# address_LEDs.net
KiCad netlist of a schematic drawn in Altium Designer
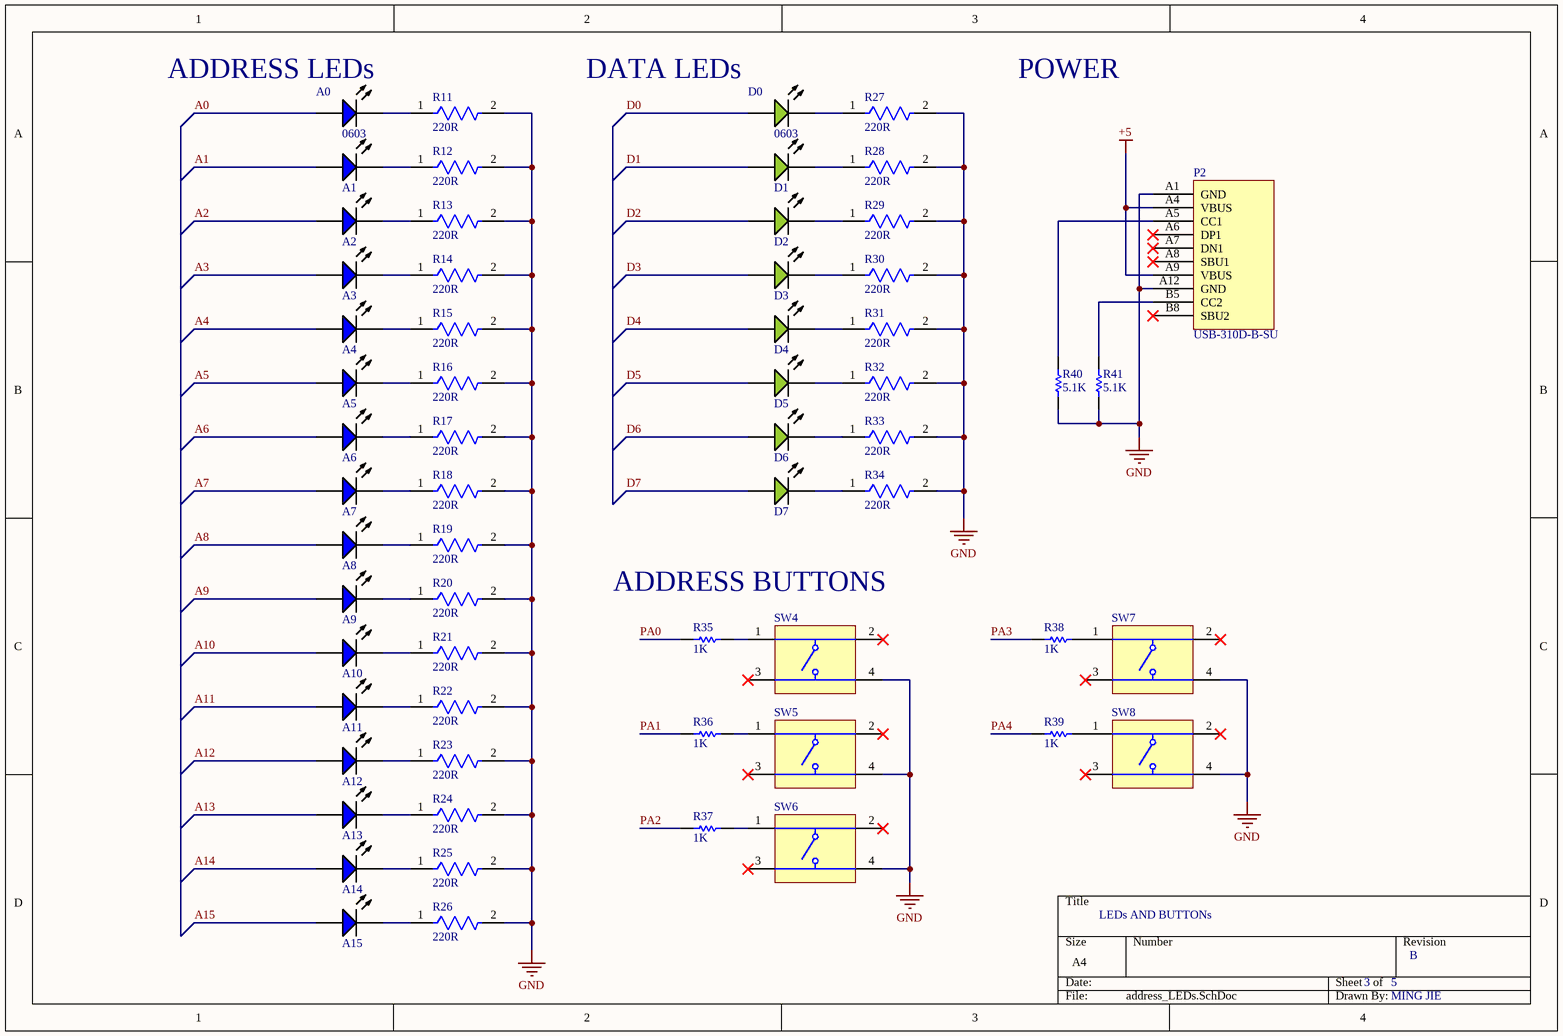
[diagram p0: address_LEDs.SchDoc]

(export (version "E")
  (design (tool "Eeschema 10.0.6"))
  (components
    (comp (ref "A0")
      (value "19-217/BHC-ZL1M2RY/3T")
      (footprint "EVRL-0603-2_V")
      (description "Chip LED, Blue, 5 V, 25 mA, -40 to 85 degC, 2-Pin SMD (0603), RoHS, Tape and Reel")
      (fields (field (name "PACKAGE REFERENCE") "0603") (field (name "MANUFACTURER") "Everlight Electronics"))
      (libsource (lib "Altium Content Vault") (part "LED-BLUE-AK-2"))
    )
    (comp (ref "A1")
      (value "19-217/BHC-ZL1M2RY/3T")
      (footprint "EVRL-0603-2_V")
      (description "Chip LED, Blue, 5 V, 25 mA, -40 to 85 degC, 2-Pin SMD (0603), RoHS, Tape and Reel")
      (fields (field (name "MANUFACTURER") "Everlight Electronics"))
      (libsource (lib "Altium Content Vault") (part "LED-BLUE-AK-2"))
    )
    (comp (ref "A2")
      (value "19-217/BHC-ZL1M2RY/3T")
      (footprint "EVRL-0603-2_V")
      (description "Chip LED, Blue, 5 V, 25 mA, -40 to 85 degC, 2-Pin SMD (0603), RoHS, Tape and Reel")
      (fields (field (name "MANUFACTURER") "Everlight Electronics"))
      (libsource (lib "Altium Content Vault") (part "LED-BLUE-AK-2"))
    )
    (comp (ref "A3")
      (value "19-217/BHC-ZL1M2RY/3T")
      (footprint "EVRL-0603-2_V")
      (description "Chip LED, Blue, 5 V, 25 mA, -40 to 85 degC, 2-Pin SMD (0603), RoHS, Tape and Reel")
      (fields (field (name "MANUFACTURER") "Everlight Electronics"))
      (libsource (lib "Altium Content Vault") (part "LED-BLUE-AK-2"))
    )
    (comp (ref "A4")
      (value "19-217/BHC-ZL1M2RY/3T")
      (footprint "EVRL-0603-2_V")
      (description "Chip LED, Blue, 5 V, 25 mA, -40 to 85 degC, 2-Pin SMD (0603), RoHS, Tape and Reel")
      (fields (field (name "MANUFACTURER") "Everlight Electronics"))
      (libsource (lib "Altium Content Vault") (part "LED-BLUE-AK-2"))
    )
    (comp (ref "A5")
      (value "19-217/BHC-ZL1M2RY/3T")
      (footprint "EVRL-0603-2_V")
      (description "Chip LED, Blue, 5 V, 25 mA, -40 to 85 degC, 2-Pin SMD (0603), RoHS, Tape and Reel")
      (fields (field (name "MANUFACTURER") "Everlight Electronics"))
      (libsource (lib "Altium Content Vault") (part "LED-BLUE-AK-2"))
    )
    (comp (ref "A6")
      (value "19-217/BHC-ZL1M2RY/3T")
      (footprint "EVRL-0603-2_V")
      (description "Chip LED, Blue, 5 V, 25 mA, -40 to 85 degC, 2-Pin SMD (0603), RoHS, Tape and Reel")
      (fields (field (name "MANUFACTURER") "Everlight Electronics"))
      (libsource (lib "Altium Content Vault") (part "LED-BLUE-AK-2"))
    )
    (comp (ref "A7")
      (value "19-217/BHC-ZL1M2RY/3T")
      (footprint "EVRL-0603-2_V")
      (description "Chip LED, Blue, 5 V, 25 mA, -40 to 85 degC, 2-Pin SMD (0603), RoHS, Tape and Reel")
      (fields (field (name "MANUFACTURER") "Everlight Electronics"))
      (libsource (lib "Altium Content Vault") (part "LED-BLUE-AK-2"))
    )
    (comp (ref "A8")
      (value "19-217/BHC-ZL1M2RY/3T")
      (footprint "EVRL-0603-2_V")
      (description "Chip LED, Blue, 5 V, 25 mA, -40 to 85 degC, 2-Pin SMD (0603), RoHS, Tape and Reel")
      (fields (field (name "MANUFACTURER") "Everlight Electronics"))
      (libsource (lib "Altium Content Vault") (part "LED-BLUE-AK-2"))
    )
    (comp (ref "A9")
      (value "19-217/BHC-ZL1M2RY/3T")
      (footprint "EVRL-0603-2_V")
      (description "Chip LED, Blue, 5 V, 25 mA, -40 to 85 degC, 2-Pin SMD (0603), RoHS, Tape and Reel")
      (fields (field (name "MANUFACTURER") "Everlight Electronics"))
      (libsource (lib "Altium Content Vault") (part "LED-BLUE-AK-2"))
    )
    (comp (ref "A10")
      (value "19-217/BHC-ZL1M2RY/3T")
      (footprint "EVRL-0603-2_V")
      (description "Chip LED, Blue, 5 V, 25 mA, -40 to 85 degC, 2-Pin SMD (0603), RoHS, Tape and Reel")
      (fields (field (name "MANUFACTURER") "Everlight Electronics"))
      (libsource (lib "Altium Content Vault") (part "LED-BLUE-AK-2"))
    )
    (comp (ref "A11")
      (value "19-217/BHC-ZL1M2RY/3T")
      (footprint "EVRL-0603-2_V")
      (description "Chip LED, Blue, 5 V, 25 mA, -40 to 85 degC, 2-Pin SMD (0603), RoHS, Tape and Reel")
      (fields (field (name "MANUFACTURER") "Everlight Electronics"))
      (libsource (lib "Altium Content Vault") (part "LED-BLUE-AK-2"))
    )
    (comp (ref "A12")
      (value "19-217/BHC-ZL1M2RY/3T")
      (footprint "EVRL-0603-2_V")
      (description "Chip LED, Blue, 5 V, 25 mA, -40 to 85 degC, 2-Pin SMD (0603), RoHS, Tape and Reel")
      (fields (field (name "MANUFACTURER") "Everlight Electronics"))
      (libsource (lib "Altium Content Vault") (part "LED-BLUE-AK-2"))
    )
    (comp (ref "A13")
      (value "19-217/BHC-ZL1M2RY/3T")
      (footprint "EVRL-0603-2_V")
      (description "Chip LED, Blue, 5 V, 25 mA, -40 to 85 degC, 2-Pin SMD (0603), RoHS, Tape and Reel")
      (fields (field (name "MANUFACTURER") "Everlight Electronics"))
      (libsource (lib "Altium Content Vault") (part "LED-BLUE-AK-2"))
    )
    (comp (ref "A14")
      (value "19-217/BHC-ZL1M2RY/3T")
      (footprint "EVRL-0603-2_V")
      (description "Chip LED, Blue, 5 V, 25 mA, -40 to 85 degC, 2-Pin SMD (0603), RoHS, Tape and Reel")
      (fields (field (name "MANUFACTURER") "Everlight Electronics"))
      (libsource (lib "Altium Content Vault") (part "LED-BLUE-AK-2"))
    )
    (comp (ref "A15")
      (value "19-217/BHC-ZL1M2RY/3T")
      (footprint "EVRL-0603-2_V")
      (description "Chip LED, Blue, 5 V, 25 mA, -40 to 85 degC, 2-Pin SMD (0603), RoHS, Tape and Reel")
      (fields (field (name "MANUFACTURER") "Everlight Electronics"))
      (libsource (lib "Altium Content Vault") (part "LED-BLUE-AK-2"))
    )
    (comp (ref "D0")
      (value "19-217/GHC-YR1S2/3T")
      (footprint "EVRL-0603-2_V")
      (description "Green 520~535nm 0603 Light Emitting Diodes (LED) RoHS")
      (fields (field (name "MANUFACTURER") "Everlight Electronics") (field (name "PACKAGE REFERENCE") "0603"))
      (libsource (lib "Altium Content Vault") (part "LED-YELLOW-GREEN-AK-2"))
    )
    (comp (ref "D1")
      (value "19-217/GHC-YR1S2/3T")
      (footprint "EVRL-0603-2_V")
      (description "Green 520~535nm 0603 Light Emitting Diodes (LED) RoHS")
      (fields (field (name "MANUFACTURER") "Everlight Electronics"))
      (libsource (lib "Altium Content Vault") (part "LED-YELLOW-GREEN-AK-2"))
    )
    (comp (ref "D2")
      (value "19-217/GHC-YR1S2/3T")
      (footprint "EVRL-0603-2_V")
      (description "Green 520~535nm 0603 Light Emitting Diodes (LED) RoHS")
      (fields (field (name "MANUFACTURER") "Everlight Electronics"))
      (libsource (lib "Altium Content Vault") (part "LED-YELLOW-GREEN-AK-2"))
    )
    (comp (ref "D3")
      (value "19-217/GHC-YR1S2/3T")
      (footprint "EVRL-0603-2_V")
      (description "Green 520~535nm 0603 Light Emitting Diodes (LED) RoHS")
      (fields (field (name "MANUFACTURER") "Everlight Electronics"))
      (libsource (lib "Altium Content Vault") (part "LED-YELLOW-GREEN-AK-2"))
    )
    (comp (ref "D4")
      (value "19-217/GHC-YR1S2/3T")
      (footprint "EVRL-0603-2_V")
      (description "Green 520~535nm 0603 Light Emitting Diodes (LED) RoHS")
      (fields (field (name "MANUFACTURER") "Everlight Electronics"))
      (libsource (lib "Altium Content Vault") (part "LED-YELLOW-GREEN-AK-2"))
    )
    (comp (ref "D5")
      (value "19-217/GHC-YR1S2/3T")
      (footprint "EVRL-0603-2_V")
      (description "Green 520~535nm 0603 Light Emitting Diodes (LED) RoHS")
      (fields (field (name "MANUFACTURER") "Everlight Electronics"))
      (libsource (lib "Altium Content Vault") (part "LED-YELLOW-GREEN-AK-2"))
    )
    (comp (ref "D6")
      (value "19-217/GHC-YR1S2/3T")
      (footprint "EVRL-0603-2_V")
      (description "Green 520~535nm 0603 Light Emitting Diodes (LED) RoHS")
      (fields (field (name "MANUFACTURER") "Everlight Electronics"))
      (libsource (lib "Altium Content Vault") (part "LED-YELLOW-GREEN-AK-2"))
    )
    (comp (ref "D7")
      (value "19-217/GHC-YR1S2/3T")
      (footprint "EVRL-0603-2_V")
      (description "Green 520~535nm 0603 Light Emitting Diodes (LED) RoHS")
      (fields (field (name "MANUFACTURER") "Everlight Electronics"))
      (libsource (lib "Altium Content Vault") (part "LED-YELLOW-GREEN-AK-2"))
    )
    (comp (ref "P2")
      (value "USB-310D-B-SU")
      (footprint "USB-C-THT")
      (description "USB Type C Receptacle")
      (libsource (lib "6502_lib") (part "USB-310D-B-SU"))
    )
    (comp (ref "R11")
      (value "CRCW0805220RFKEA")
      (footprint "FP-CRCW0805-e3-MFG")
      (description "RES Thick Film, 220Ω, 1%, 0.125W, 100ppm/°C, 0805")
      (fields (field (name "RESISTANCE") "220R") (field (name "TOLERANCE") "1%"))
      (libsource (lib "Altium Content Vault") (part "1029c3af85768c4190bb7ad29bc67b5"))
    )
    (comp (ref "R12")
      (value "CRCW0805220RFKEA")
      (footprint "FP-CRCW0805-e3-MFG")
      (description "RES Thick Film, 220Ω, 1%, 0.125W, 100ppm/°C, 0805")
      (fields (field (name "RESISTANCE") "220R") (field (name "TOLERANCE") "1%"))
      (libsource (lib "Altium Content Vault") (part "1029c3af85768c4190bb7ad29bc67b5"))
    )
    (comp (ref "R13")
      (value "CRCW0805220RFKEA")
      (footprint "FP-CRCW0805-e3-MFG")
      (description "RES Thick Film, 220Ω, 1%, 0.125W, 100ppm/°C, 0805")
      (fields (field (name "RESISTANCE") "220R") (field (name "TOLERANCE") "1%"))
      (libsource (lib "Altium Content Vault") (part "1029c3af85768c4190bb7ad29bc67b5"))
    )
    (comp (ref "R14")
      (value "CRCW0805220RFKEA")
      (footprint "FP-CRCW0805-e3-MFG")
      (description "RES Thick Film, 220Ω, 1%, 0.125W, 100ppm/°C, 0805")
      (fields (field (name "RESISTANCE") "220R") (field (name "TOLERANCE") "1%"))
      (libsource (lib "Altium Content Vault") (part "1029c3af85768c4190bb7ad29bc67b5"))
    )
    (comp (ref "R15")
      (value "CRCW0805220RFKEA")
      (footprint "FP-CRCW0805-e3-MFG")
      (description "RES Thick Film, 220Ω, 1%, 0.125W, 100ppm/°C, 0805")
      (fields (field (name "RESISTANCE") "220R") (field (name "TOLERANCE") "1%"))
      (libsource (lib "Altium Content Vault") (part "1029c3af85768c4190bb7ad29bc67b5"))
    )
    (comp (ref "R16")
      (value "CRCW0805220RFKEA")
      (footprint "FP-CRCW0805-e3-MFG")
      (description "RES Thick Film, 220Ω, 1%, 0.125W, 100ppm/°C, 0805")
      (fields (field (name "RESISTANCE") "220R") (field (name "TOLERANCE") "1%"))
      (libsource (lib "Altium Content Vault") (part "1029c3af85768c4190bb7ad29bc67b5"))
    )
    (comp (ref "R17")
      (value "CRCW0805220RFKEA")
      (footprint "FP-CRCW0805-e3-MFG")
      (description "RES Thick Film, 220Ω, 1%, 0.125W, 100ppm/°C, 0805")
      (fields (field (name "RESISTANCE") "220R") (field (name "TOLERANCE") "1%"))
      (libsource (lib "Altium Content Vault") (part "1029c3af85768c4190bb7ad29bc67b5"))
    )
    (comp (ref "R18")
      (value "CRCW0805220RFKEA")
      (footprint "FP-CRCW0805-e3-MFG")
      (description "RES Thick Film, 220Ω, 1%, 0.125W, 100ppm/°C, 0805")
      (fields (field (name "RESISTANCE") "220R") (field (name "TOLERANCE") "1%"))
      (libsource (lib "Altium Content Vault") (part "1029c3af85768c4190bb7ad29bc67b5"))
    )
    (comp (ref "R19")
      (value "CRCW0805220RFKEA")
      (footprint "FP-CRCW0805-e3-MFG")
      (description "RES Thick Film, 220Ω, 1%, 0.125W, 100ppm/°C, 0805")
      (fields (field (name "RESISTANCE") "220R") (field (name "TOLERANCE") "1%"))
      (libsource (lib "Altium Content Vault") (part "1029c3af85768c4190bb7ad29bc67b5"))
    )
    (comp (ref "R20")
      (value "CRCW0805220RFKEA")
      (footprint "FP-CRCW0805-e3-MFG")
      (description "RES Thick Film, 220Ω, 1%, 0.125W, 100ppm/°C, 0805")
      (fields (field (name "RESISTANCE") "220R") (field (name "TOLERANCE") "1%"))
      (libsource (lib "Altium Content Vault") (part "1029c3af85768c4190bb7ad29bc67b5"))
    )
    (comp (ref "R21")
      (value "CRCW0805220RFKEA")
      (footprint "FP-CRCW0805-e3-MFG")
      (description "RES Thick Film, 220Ω, 1%, 0.125W, 100ppm/°C, 0805")
      (fields (field (name "RESISTANCE") "220R") (field (name "TOLERANCE") "1%"))
      (libsource (lib "Altium Content Vault") (part "1029c3af85768c4190bb7ad29bc67b5"))
    )
    (comp (ref "R22")
      (value "CRCW0805220RFKEA")
      (footprint "FP-CRCW0805-e3-MFG")
      (description "RES Thick Film, 220Ω, 1%, 0.125W, 100ppm/°C, 0805")
      (fields (field (name "RESISTANCE") "220R") (field (name "TOLERANCE") "1%"))
      (libsource (lib "Altium Content Vault") (part "1029c3af85768c4190bb7ad29bc67b5"))
    )
    (comp (ref "R23")
      (value "CRCW0805220RFKEA")
      (footprint "FP-CRCW0805-e3-MFG")
      (description "RES Thick Film, 220Ω, 1%, 0.125W, 100ppm/°C, 0805")
      (fields (field (name "RESISTANCE") "220R") (field (name "TOLERANCE") "1%"))
      (libsource (lib "Altium Content Vault") (part "1029c3af85768c4190bb7ad29bc67b5"))
    )
    (comp (ref "R24")
      (value "CRCW0805220RFKEA")
      (footprint "FP-CRCW0805-e3-MFG")
      (description "RES Thick Film, 220Ω, 1%, 0.125W, 100ppm/°C, 0805")
      (fields (field (name "RESISTANCE") "220R") (field (name "TOLERANCE") "1%"))
      (libsource (lib "Altium Content Vault") (part "1029c3af85768c4190bb7ad29bc67b5"))
    )
    (comp (ref "R25")
      (value "CRCW0805220RFKEA")
      (footprint "FP-CRCW0805-e3-MFG")
      (description "RES Thick Film, 220Ω, 1%, 0.125W, 100ppm/°C, 0805")
      (fields (field (name "RESISTANCE") "220R") (field (name "TOLERANCE") "1%"))
      (libsource (lib "Altium Content Vault") (part "1029c3af85768c4190bb7ad29bc67b5"))
    )
    (comp (ref "R26")
      (value "CRCW0805220RFKEA")
      (footprint "FP-CRCW0805-e3-MFG")
      (description "RES Thick Film, 220Ω, 1%, 0.125W, 100ppm/°C, 0805")
      (fields (field (name "RESISTANCE") "220R") (field (name "TOLERANCE") "1%"))
      (libsource (lib "Altium Content Vault") (part "1029c3af85768c4190bb7ad29bc67b5"))
    )
    (comp (ref "R27")
      (value "CRCW0805220RFKEA")
      (footprint "FP-CRCW0805-e3-MFG")
      (description "RES Thick Film, 220Ω, 1%, 0.125W, 100ppm/°C, 0805")
      (fields (field (name "RESISTANCE") "220R") (field (name "TOLERANCE") "1%"))
      (libsource (lib "Altium Content Vault") (part "1029c3af85768c4190bb7ad29bc67b5"))
    )
    (comp (ref "R28")
      (value "CRCW0805220RFKEA")
      (footprint "FP-CRCW0805-e3-MFG")
      (description "RES Thick Film, 220Ω, 1%, 0.125W, 100ppm/°C, 0805")
      (fields (field (name "RESISTANCE") "220R") (field (name "TOLERANCE") "1%"))
      (libsource (lib "Altium Content Vault") (part "1029c3af85768c4190bb7ad29bc67b5"))
    )
    (comp (ref "R29")
      (value "CRCW0805220RFKEA")
      (footprint "FP-CRCW0805-e3-MFG")
      (description "RES Thick Film, 220Ω, 1%, 0.125W, 100ppm/°C, 0805")
      (fields (field (name "RESISTANCE") "220R") (field (name "TOLERANCE") "1%"))
      (libsource (lib "Altium Content Vault") (part "1029c3af85768c4190bb7ad29bc67b5"))
    )
    (comp (ref "R30")
      (value "CRCW0805220RFKEA")
      (footprint "FP-CRCW0805-e3-MFG")
      (description "RES Thick Film, 220Ω, 1%, 0.125W, 100ppm/°C, 0805")
      (fields (field (name "RESISTANCE") "220R") (field (name "TOLERANCE") "1%"))
      (libsource (lib "Altium Content Vault") (part "1029c3af85768c4190bb7ad29bc67b5"))
    )
    (comp (ref "R31")
      (value "CRCW0805220RFKEA")
      (footprint "FP-CRCW0805-e3-MFG")
      (description "RES Thick Film, 220Ω, 1%, 0.125W, 100ppm/°C, 0805")
      (fields (field (name "RESISTANCE") "220R") (field (name "TOLERANCE") "1%"))
      (libsource (lib "Altium Content Vault") (part "1029c3af85768c4190bb7ad29bc67b5"))
    )
    (comp (ref "R32")
      (value "CRCW0805220RFKEA")
      (footprint "FP-CRCW0805-e3-MFG")
      (description "RES Thick Film, 220Ω, 1%, 0.125W, 100ppm/°C, 0805")
      (fields (field (name "RESISTANCE") "220R") (field (name "TOLERANCE") "1%"))
      (libsource (lib "Altium Content Vault") (part "1029c3af85768c4190bb7ad29bc67b5"))
    )
    (comp (ref "R33")
      (value "CRCW0805220RFKEA")
      (footprint "FP-CRCW0805-e3-MFG")
      (description "RES Thick Film, 220Ω, 1%, 0.125W, 100ppm/°C, 0805")
      (fields (field (name "RESISTANCE") "220R") (field (name "TOLERANCE") "1%"))
      (libsource (lib "Altium Content Vault") (part "1029c3af85768c4190bb7ad29bc67b5"))
    )
    (comp (ref "R34")
      (value "CRCW0805220RFKEA")
      (footprint "FP-CRCW0805-e3-MFG")
      (description "RES Thick Film, 220Ω, 1%, 0.125W, 100ppm/°C, 0805")
      (fields (field (name "RESISTANCE") "220R") (field (name "TOLERANCE") "1%"))
      (libsource (lib "Altium Content Vault") (part "1029c3af85768c4190bb7ad29bc67b5"))
    )
    (comp (ref "R35")
      (value "CRCW08051K00FKEA")
      (footprint "RESC2013X50X30NL20T20")
      (fields (field (name "MANUFACTURER") "Vishay Dale") (field (name "RESISTANCE") "1K"))
      (libsource (lib "Altium Content Vault") (part "RES"))
    )
    (comp (ref "R36")
      (value "CRCW08051K00FKEA")
      (footprint "RESC2013X50X30NL20T20")
      (fields (field (name "MANUFACTURER") "Vishay Dale") (field (name "RESISTANCE") "1K"))
      (libsource (lib "Altium Content Vault") (part "RES"))
    )
    (comp (ref "R37")
      (value "CRCW08051K00FKEA")
      (footprint "RESC2013X50X30NL20T20")
      (fields (field (name "MANUFACTURER") "Vishay Dale") (field (name "RESISTANCE") "1K"))
      (libsource (lib "Altium Content Vault") (part "RES"))
    )
    (comp (ref "R38")
      (value "CRCW08051K00FKEA")
      (footprint "RESC2013X50X30NL20T20")
      (fields (field (name "MANUFACTURER") "Vishay Dale") (field (name "RESISTANCE") "1K"))
      (libsource (lib "Altium Content Vault") (part "RES"))
    )
    (comp (ref "R39")
      (value "CRCW08051K00FKEA")
      (footprint "RESC2013X50X30NL20T20")
      (fields (field (name "MANUFACTURER") "Vishay Dale") (field (name "RESISTANCE") "1K"))
      (libsource (lib "Altium Content Vault") (part "RES"))
    )
    (comp (ref "R40")
      (value "0805W8F5101T5E")
      (footprint "RESC2013X50X30NL20T20")
      (description "5.1kΩ ±1% 0.125W ±100ppm/℃ 0805 Chip Resistor - Surface Mount RoHS")
      (fields (field (name "MANUFACTURER") "UniOhm") (field (name "RESISTANCE") "5.1K"))
      (libsource (lib "Altium Content Vault") (part "RES"))
    )
    (comp (ref "R41")
      (value "0805W8F5101T5E")
      (footprint "RESC2013X50X30NL20T20")
      (description "5.1kΩ ±1% 0.125W ±100ppm/℃ 0805 Chip Resistor - Surface Mount RoHS")
      (fields (field (name "MANUFACTURER") "UniOhm") (field (name "RESISTANCE") "5.1K"))
      (libsource (lib "Altium Content Vault") (part "RES"))
    )
    (comp (ref "SW4")
      (value "K2-1102SP-C4SC-04")
      (footprint "TECO-FSM4JSMA_V")
      (description "Swicth, SPST, 24 V, -35 to 85 degC, 4-Pin SMD, RoHS, Tape and Reel")
      (fields (field (name "MANUFACTURER") "TE Connectivity"))
      (libsource (lib "Altium Content Vault") (part "SW-SPST-4_A"))
    )
    (comp (ref "SW5")
      (value "K2-1102SP-C4SC-04")
      (footprint "TECO-FSM4JSMA_V")
      (description "Swicth, SPST, 24 V, -35 to 85 degC, 4-Pin SMD, RoHS, Tape and Reel")
      (fields (field (name "MANUFACTURER") "TE Connectivity"))
      (libsource (lib "Altium Content Vault") (part "SW-SPST-4_A"))
    )
    (comp (ref "SW6")
      (value "K2-1102SP-C4SC-04")
      (footprint "TECO-FSM4JSMA_V")
      (description "Swicth, SPST, 24 V, -35 to 85 degC, 4-Pin SMD, RoHS, Tape and Reel")
      (fields (field (name "MANUFACTURER") "TE Connectivity"))
      (libsource (lib "Altium Content Vault") (part "SW-SPST-4_A"))
    )
    (comp (ref "SW7")
      (value "K2-1102SP-C4SC-04")
      (footprint "TECO-FSM4JSMA_V")
      (description "Swicth, SPST, 24 V, -35 to 85 degC, 4-Pin SMD, RoHS, Tape and Reel")
      (fields (field (name "MANUFACTURER") "TE Connectivity"))
      (libsource (lib "Altium Content Vault") (part "SW-SPST-4_A"))
    )
    (comp (ref "SW8")
      (value "K2-1102SP-C4SC-04")
      (footprint "TECO-FSM4JSMA_V")
      (description "Swicth, SPST, 24 V, -35 to 85 degC, 4-Pin SMD, RoHS, Tape and Reel")
      (fields (field (name "MANUFACTURER") "TE Connectivity"))
      (libsource (lib "Altium Content Vault") (part "SW-SPST-4_A"))
    )
  )
  (nets
    (net (code "1") (name "+5") (class "Default")
      (node (ref "P2") (pin "A4") (pinfunction "VBUS_A4") (pintype "passive"))
      (node (ref "P2") (pin "A9") (pinfunction "VBUS_A9") (pintype "passive"))
    )
    (net (code "2") (name "/A0") (class "Default")
      (node (ref "A0") (pin "1") (pinfunction "A_1") (pintype "passive"))
    )
    (net (code "3") (name "/A1") (class "Default")
      (node (ref "A1") (pin "1") (pinfunction "A_1") (pintype "passive"))
    )
    (net (code "4") (name "/A2") (class "Default")
      (node (ref "A2") (pin "1") (pinfunction "A_1") (pintype "passive"))
    )
    (net (code "5") (name "/A3") (class "Default")
      (node (ref "A3") (pin "1") (pinfunction "A_1") (pintype "passive"))
    )
    (net (code "6") (name "/A4") (class "Default")
      (node (ref "A4") (pin "1") (pinfunction "A_1") (pintype "passive"))
    )
    (net (code "7") (name "/A5") (class "Default")
      (node (ref "A5") (pin "1") (pinfunction "A_1") (pintype "passive"))
    )
    (net (code "8") (name "/A6") (class "Default")
      (node (ref "A6") (pin "1") (pinfunction "A_1") (pintype "passive"))
    )
    (net (code "9") (name "/A7") (class "Default")
      (node (ref "A7") (pin "1") (pinfunction "A_1") (pintype "passive"))
    )
    (net (code "10") (name "/A8") (class "Default")
      (node (ref "A8") (pin "1") (pinfunction "A_1") (pintype "passive"))
    )
    (net (code "11") (name "/A9") (class "Default")
      (node (ref "A9") (pin "1") (pinfunction "A_1") (pintype "passive"))
    )
    (net (code "12") (name "/A10") (class "Default")
      (node (ref "A10") (pin "1") (pinfunction "A_1") (pintype "passive"))
    )
    (net (code "13") (name "/A11") (class "Default")
      (node (ref "A11") (pin "1") (pinfunction "A_1") (pintype "passive"))
    )
    (net (code "14") (name "/A12") (class "Default")
      (node (ref "A12") (pin "1") (pinfunction "A_1") (pintype "passive"))
    )
    (net (code "15") (name "/A13") (class "Default")
      (node (ref "A13") (pin "1") (pinfunction "A_1") (pintype "passive"))
    )
    (net (code "16") (name "/A14") (class "Default")
      (node (ref "A14") (pin "1") (pinfunction "A_1") (pintype "passive"))
    )
    (net (code "17") (name "/A15") (class "Default")
      (node (ref "A15") (pin "1") (pinfunction "A_1") (pintype "passive"))
    )
    (net (code "18") (name "/D0") (class "Default")
      (node (ref "D0") (pin "1") (pinfunction "A_1") (pintype "passive"))
    )
    (net (code "19") (name "/D1") (class "Default")
      (node (ref "D1") (pin "1") (pinfunction "A_1") (pintype "passive"))
    )
    (net (code "20") (name "/D2") (class "Default")
      (node (ref "D2") (pin "1") (pinfunction "A_1") (pintype "passive"))
    )
    (net (code "21") (name "/D3") (class "Default")
      (node (ref "D3") (pin "1") (pinfunction "A_1") (pintype "passive"))
    )
    (net (code "22") (name "/D4") (class "Default")
      (node (ref "D4") (pin "1") (pinfunction "A_1") (pintype "passive"))
    )
    (net (code "23") (name "/D5") (class "Default")
      (node (ref "D5") (pin "1") (pinfunction "A_1") (pintype "passive"))
    )
    (net (code "24") (name "/D6") (class "Default")
      (node (ref "D6") (pin "1") (pinfunction "A_1") (pintype "passive"))
    )
    (net (code "25") (name "/D7") (class "Default")
      (node (ref "D7") (pin "1") (pinfunction "A_1") (pintype "passive"))
    )
    (net (code "26") (name "/PA0") (class "Default")
      (node (ref "R35") (pin "1") (pinfunction "1_1") (pintype "passive"))
    )
    (net (code "27") (name "/PA1") (class "Default")
      (node (ref "R36") (pin "1") (pinfunction "1_1") (pintype "passive"))
    )
    (net (code "28") (name "/PA2") (class "Default")
      (node (ref "R37") (pin "1") (pinfunction "1_1") (pintype "passive"))
    )
    (net (code "29") (name "/PA3") (class "Default")
      (node (ref "R38") (pin "1") (pinfunction "1_1") (pintype "passive"))
    )
    (net (code "30") (name "/PA4") (class "Default")
      (node (ref "R39") (pin "1") (pinfunction "1_1") (pintype "passive"))
    )
    (net (code "31") (name "GND") (class "Default")
      (node (ref "P2") (pin "A1") (pinfunction "GND_A1") (pintype "passive"))
      (node (ref "P2") (pin "A12") (pinfunction "GND_A12") (pintype "passive"))
      (node (ref "R11") (pin "2") (pinfunction "2_2") (pintype "passive"))
      (node (ref "R12") (pin "2") (pinfunction "2_2") (pintype "passive"))
      (node (ref "R13") (pin "2") (pinfunction "2_2") (pintype "passive"))
      (node (ref "R14") (pin "2") (pinfunction "2_2") (pintype "passive"))
      (node (ref "R15") (pin "2") (pinfunction "2_2") (pintype "passive"))
      (node (ref "R16") (pin "2") (pinfunction "2_2") (pintype "passive"))
      (node (ref "R17") (pin "2") (pinfunction "2_2") (pintype "passive"))
      (node (ref "R18") (pin "2") (pinfunction "2_2") (pintype "passive"))
      (node (ref "R19") (pin "2") (pinfunction "2_2") (pintype "passive"))
      (node (ref "R20") (pin "2") (pinfunction "2_2") (pintype "passive"))
      (node (ref "R21") (pin "2") (pinfunction "2_2") (pintype "passive"))
      (node (ref "R22") (pin "2") (pinfunction "2_2") (pintype "passive"))
      (node (ref "R23") (pin "2") (pinfunction "2_2") (pintype "passive"))
      (node (ref "R24") (pin "2") (pinfunction "2_2") (pintype "passive"))
      (node (ref "R25") (pin "2") (pinfunction "2_2") (pintype "passive"))
      (node (ref "R26") (pin "2") (pinfunction "2_2") (pintype "passive"))
      (node (ref "R27") (pin "2") (pinfunction "2_2") (pintype "passive"))
      (node (ref "R28") (pin "2") (pinfunction "2_2") (pintype "passive"))
      (node (ref "R29") (pin "2") (pinfunction "2_2") (pintype "passive"))
      (node (ref "R30") (pin "2") (pinfunction "2_2") (pintype "passive"))
      (node (ref "R31") (pin "2") (pinfunction "2_2") (pintype "passive"))
      (node (ref "R32") (pin "2") (pinfunction "2_2") (pintype "passive"))
      (node (ref "R33") (pin "2") (pinfunction "2_2") (pintype "passive"))
      (node (ref "R34") (pin "2") (pinfunction "2_2") (pintype "passive"))
      (node (ref "R40") (pin "1") (pinfunction "1_1") (pintype "passive"))
      (node (ref "R41") (pin "1") (pinfunction "1_1") (pintype "passive"))
      (node (ref "SW4") (pin "4") (pinfunction "4_4") (pintype "passive"))
      (node (ref "SW5") (pin "4") (pinfunction "4_4") (pintype "passive"))
      (node (ref "SW6") (pin "4") (pinfunction "4_4") (pintype "passive"))
      (node (ref "SW7") (pin "4") (pinfunction "4_4") (pintype "passive"))
      (node (ref "SW8") (pin "4") (pinfunction "4_4") (pintype "passive"))
    )
    (net (code "32") (name "Net-(A0-K)") (class "Default")
      (node (ref "A0") (pin "2") (pinfunction "K_2") (pintype "passive"))
      (node (ref "R11") (pin "1") (pinfunction "1_1") (pintype "passive"))
    )
    (net (code "33") (name "Net-(A1-K)") (class "Default")
      (node (ref "A1") (pin "2") (pinfunction "K_2") (pintype "passive"))
      (node (ref "R12") (pin "1") (pinfunction "1_1") (pintype "passive"))
    )
    (net (code "34") (name "Net-(A2-K)") (class "Default")
      (node (ref "A2") (pin "2") (pinfunction "K_2") (pintype "passive"))
      (node (ref "R13") (pin "1") (pinfunction "1_1") (pintype "passive"))
    )
    (net (code "35") (name "Net-(A3-K)") (class "Default")
      (node (ref "A3") (pin "2") (pinfunction "K_2") (pintype "passive"))
      (node (ref "R14") (pin "1") (pinfunction "1_1") (pintype "passive"))
    )
    (net (code "36") (name "Net-(A4-K)") (class "Default")
      (node (ref "A4") (pin "2") (pinfunction "K_2") (pintype "passive"))
      (node (ref "R15") (pin "1") (pinfunction "1_1") (pintype "passive"))
    )
    (net (code "37") (name "Net-(A5-K)") (class "Default")
      (node (ref "A5") (pin "2") (pinfunction "K_2") (pintype "passive"))
      (node (ref "R16") (pin "1") (pinfunction "1_1") (pintype "passive"))
    )
    (net (code "38") (name "Net-(A6-K)") (class "Default")
      (node (ref "A6") (pin "2") (pinfunction "K_2") (pintype "passive"))
      (node (ref "R17") (pin "1") (pinfunction "1_1") (pintype "passive"))
    )
    (net (code "39") (name "Net-(A7-K)") (class "Default")
      (node (ref "A7") (pin "2") (pinfunction "K_2") (pintype "passive"))
      (node (ref "R18") (pin "1") (pinfunction "1_1") (pintype "passive"))
    )
    (net (code "40") (name "Net-(A8-K)") (class "Default")
      (node (ref "A8") (pin "2") (pinfunction "K_2") (pintype "passive"))
      (node (ref "R19") (pin "1") (pinfunction "1_1") (pintype "passive"))
    )
    (net (code "41") (name "Net-(A9-K)") (class "Default")
      (node (ref "A9") (pin "2") (pinfunction "K_2") (pintype "passive"))
      (node (ref "R20") (pin "1") (pinfunction "1_1") (pintype "passive"))
    )
    (net (code "42") (name "Net-(A10-K)") (class "Default")
      (node (ref "A10") (pin "2") (pinfunction "K_2") (pintype "passive"))
      (node (ref "R21") (pin "1") (pinfunction "1_1") (pintype "passive"))
    )
    (net (code "43") (name "Net-(A11-K)") (class "Default")
      (node (ref "A11") (pin "2") (pinfunction "K_2") (pintype "passive"))
      (node (ref "R22") (pin "1") (pinfunction "1_1") (pintype "passive"))
    )
    (net (code "44") (name "Net-(A12-K)") (class "Default")
      (node (ref "A12") (pin "2") (pinfunction "K_2") (pintype "passive"))
      (node (ref "R23") (pin "1") (pinfunction "1_1") (pintype "passive"))
    )
    (net (code "45") (name "Net-(A13-K)") (class "Default")
      (node (ref "A13") (pin "2") (pinfunction "K_2") (pintype "passive"))
      (node (ref "R24") (pin "1") (pinfunction "1_1") (pintype "passive"))
    )
    (net (code "46") (name "Net-(A14-K)") (class "Default")
      (node (ref "A14") (pin "2") (pinfunction "K_2") (pintype "passive"))
      (node (ref "R25") (pin "1") (pinfunction "1_1") (pintype "passive"))
    )
    (net (code "47") (name "Net-(A15-K)") (class "Default")
      (node (ref "A15") (pin "2") (pinfunction "K_2") (pintype "passive"))
      (node (ref "R26") (pin "1") (pinfunction "1_1") (pintype "passive"))
    )
    (net (code "48") (name "Net-(D0-K)") (class "Default")
      (node (ref "D0") (pin "2") (pinfunction "K_2") (pintype "passive"))
      (node (ref "R27") (pin "1") (pinfunction "1_1") (pintype "passive"))
    )
    (net (code "49") (name "Net-(D1-K)") (class "Default")
      (node (ref "D1") (pin "2") (pinfunction "K_2") (pintype "passive"))
      (node (ref "R28") (pin "1") (pinfunction "1_1") (pintype "passive"))
    )
    (net (code "50") (name "Net-(D2-K)") (class "Default")
      (node (ref "D2") (pin "2") (pinfunction "K_2") (pintype "passive"))
      (node (ref "R29") (pin "1") (pinfunction "1_1") (pintype "passive"))
    )
    (net (code "51") (name "Net-(D3-K)") (class "Default")
      (node (ref "D3") (pin "2") (pinfunction "K_2") (pintype "passive"))
      (node (ref "R30") (pin "1") (pinfunction "1_1") (pintype "passive"))
    )
    (net (code "52") (name "Net-(D4-K)") (class "Default")
      (node (ref "D4") (pin "2") (pinfunction "K_2") (pintype "passive"))
      (node (ref "R31") (pin "1") (pinfunction "1_1") (pintype "passive"))
    )
    (net (code "53") (name "Net-(D5-K)") (class "Default")
      (node (ref "D5") (pin "2") (pinfunction "K_2") (pintype "passive"))
      (node (ref "R32") (pin "1") (pinfunction "1_1") (pintype "passive"))
    )
    (net (code "54") (name "Net-(D6-K)") (class "Default")
      (node (ref "D6") (pin "2") (pinfunction "K_2") (pintype "passive"))
      (node (ref "R33") (pin "1") (pinfunction "1_1") (pintype "passive"))
    )
    (net (code "55") (name "Net-(D7-K)") (class "Default")
      (node (ref "D7") (pin "2") (pinfunction "K_2") (pintype "passive"))
      (node (ref "R34") (pin "1") (pinfunction "1_1") (pintype "passive"))
    )
    (net (code "56") (name "Net-(P2-CC1)") (class "Default")
      (node (ref "P2") (pin "A5") (pinfunction "CC1_A5") (pintype "passive"))
      (node (ref "R40") (pin "2") (pinfunction "2_2") (pintype "passive"))
    )
    (net (code "57") (name "Net-(P2-CC2)") (class "Default")
      (node (ref "P2") (pin "B5") (pinfunction "CC2_B5") (pintype "passive"))
      (node (ref "R41") (pin "2") (pinfunction "2_2") (pintype "passive"))
    )
    (net (code "58") (name "Net-(R35-Pad2)") (class "Default")
      (node (ref "R35") (pin "2") (pinfunction "2_2") (pintype "passive"))
      (node (ref "SW4") (pin "1") (pinfunction "1_1") (pintype "passive"))
    )
    (net (code "59") (name "Net-(R36-Pad2)") (class "Default")
      (node (ref "R36") (pin "2") (pinfunction "2_2") (pintype "passive"))
      (node (ref "SW5") (pin "1") (pinfunction "1_1") (pintype "passive"))
    )
    (net (code "60") (name "Net-(R37-Pad2)") (class "Default")
      (node (ref "R37") (pin "2") (pinfunction "2_2") (pintype "passive"))
      (node (ref "SW6") (pin "1") (pinfunction "1_1") (pintype "passive"))
    )
    (net (code "61") (name "Net-(R38-Pad2)") (class "Default")
      (node (ref "R38") (pin "2") (pinfunction "2_2") (pintype "passive"))
      (node (ref "SW7") (pin "1") (pinfunction "1_1") (pintype "passive"))
    )
    (net (code "62") (name "Net-(R39-Pad2)") (class "Default")
      (node (ref "R39") (pin "2") (pinfunction "2_2") (pintype "passive"))
      (node (ref "SW8") (pin "1") (pinfunction "1_1") (pintype "passive"))
    )
    (net (code "63") (name "unconnected-(P2-DN1-PadA7)") (class "Default")
      (node (ref "P2") (pin "A7") (pinfunction "DN1_A7") (pintype "passive+no_connect"))
    )
    (net (code "64") (name "unconnected-(P2-DP1-PadA6)") (class "Default")
      (node (ref "P2") (pin "A6") (pinfunction "DP1_A6") (pintype "passive+no_connect"))
    )
    (net (code "65") (name "unconnected-(P2-SBU1-PadA8)") (class "Default")
      (node (ref "P2") (pin "A8") (pinfunction "SBU1_A8") (pintype "passive+no_connect"))
    )
    (net (code "66") (name "unconnected-(P2-SBU2-PadB8)") (class "Default")
      (node (ref "P2") (pin "B8") (pinfunction "SBU2_B8") (pintype "passive+no_connect"))
    )
    (net (code "67") (name "unconnected-(SW4-Pad2)") (class "Default")
      (node (ref "SW4") (pin "2") (pinfunction "2_2") (pintype "passive+no_connect"))
    )
    (net (code "68") (name "unconnected-(SW4-Pad3)") (class "Default")
      (node (ref "SW4") (pin "3") (pinfunction "3_3") (pintype "passive+no_connect"))
    )
    (net (code "69") (name "unconnected-(SW5-Pad2)") (class "Default")
      (node (ref "SW5") (pin "2") (pinfunction "2_2") (pintype "passive+no_connect"))
    )
    (net (code "70") (name "unconnected-(SW5-Pad3)") (class "Default")
      (node (ref "SW5") (pin "3") (pinfunction "3_3") (pintype "passive+no_connect"))
    )
    (net (code "71") (name "unconnected-(SW6-Pad2)") (class "Default")
      (node (ref "SW6") (pin "2") (pinfunction "2_2") (pintype "passive+no_connect"))
    )
    (net (code "72") (name "unconnected-(SW6-Pad3)") (class "Default")
      (node (ref "SW6") (pin "3") (pinfunction "3_3") (pintype "passive+no_connect"))
    )
    (net (code "73") (name "unconnected-(SW7-Pad2)") (class "Default")
      (node (ref "SW7") (pin "2") (pinfunction "2_2") (pintype "passive+no_connect"))
    )
    (net (code "74") (name "unconnected-(SW7-Pad3)") (class "Default")
      (node (ref "SW7") (pin "3") (pinfunction "3_3") (pintype "passive+no_connect"))
    )
    (net (code "75") (name "unconnected-(SW8-Pad2)") (class "Default")
      (node (ref "SW8") (pin "2") (pinfunction "2_2") (pintype "passive+no_connect"))
    )
    (net (code "76") (name "unconnected-(SW8-Pad3)") (class "Default")
      (node (ref "SW8") (pin "3") (pinfunction "3_3") (pintype "passive+no_connect"))
    )
  )
)
